# TIDA-01485_Page2.net
KiCad netlist of a schematic drawn in Altium Designer
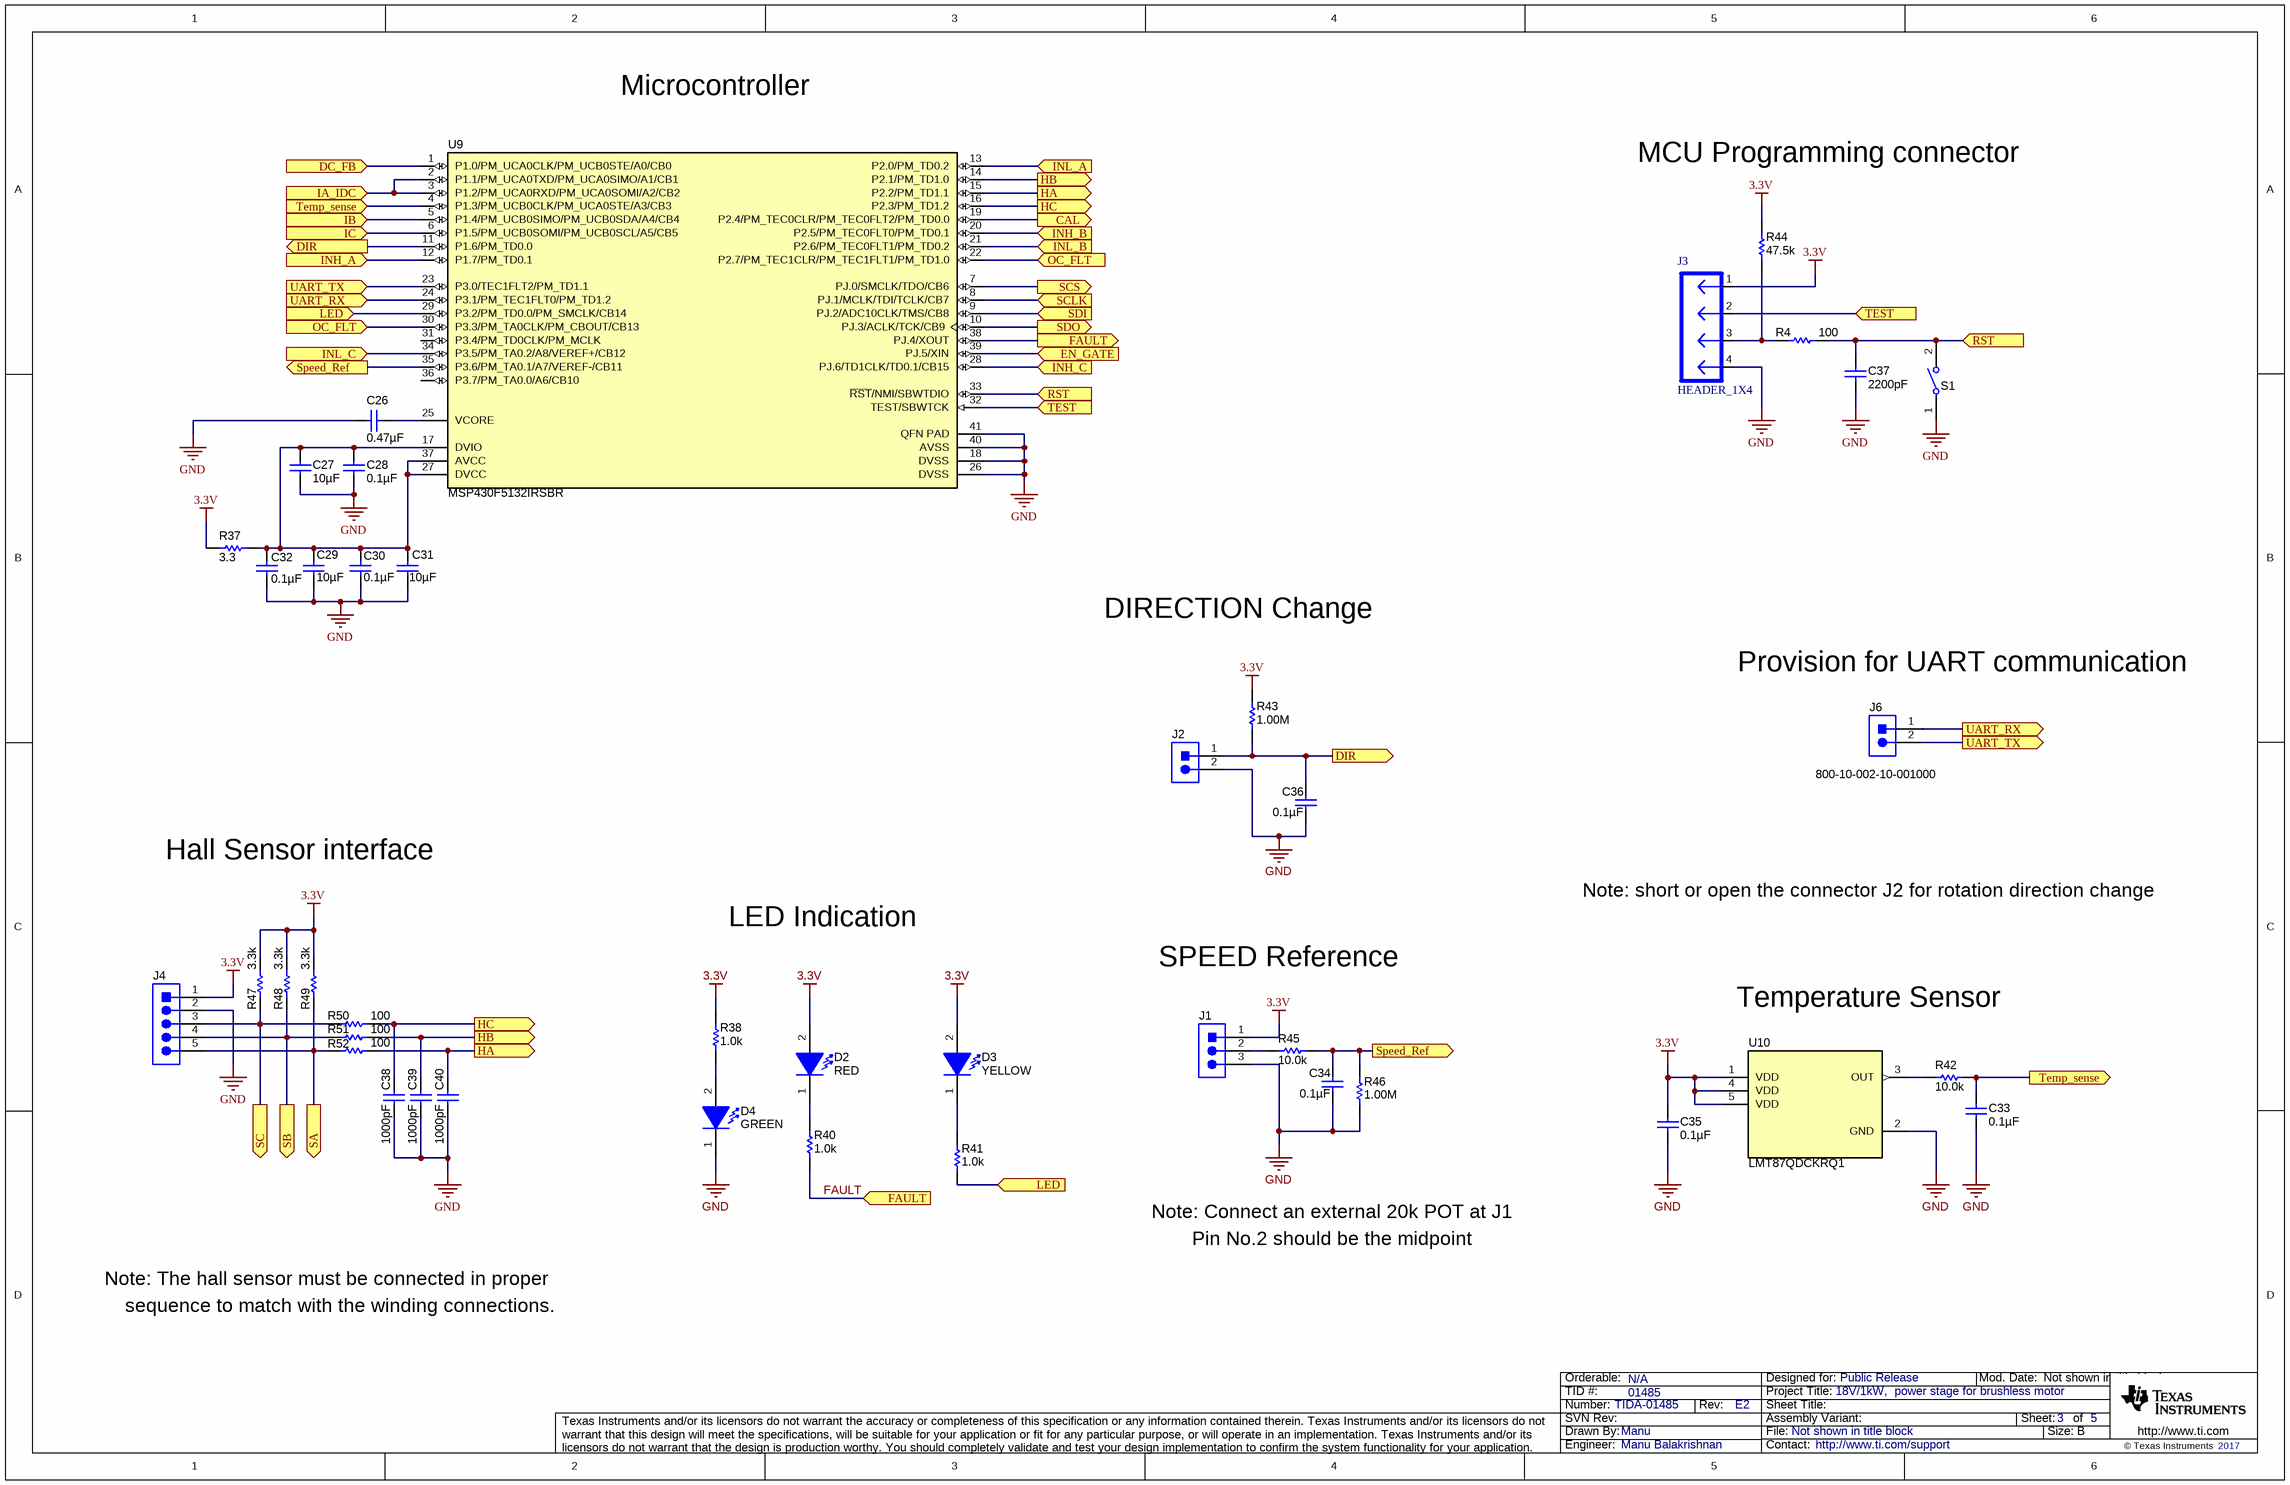
[diagram p0: TIDA-01485_Page2.SchDoc]

(export (version "E")
  (design (tool "Eeschema 10.0.6"))
  (components
    (comp (ref "C26")
      (value "C0805C474K4RACTU")
      (footprint "0805_HV")
      (description "CAP, CERM, 0.47 µF, 16 V, +/- 10%, X7R, 0805")
      (fields
        (field (name "VALUEDISPLAYED") "0.47µF")
        (field (name "MANUFACTURER") "Kemet")
        (field (name "PUBLISHER") "Texas Instruments")
      )
      (libsource (lib "Capacitor_Ceramic") (part "C0805C474K4RACTU"))
    )
    (comp (ref "C27")
      (value "0805YD106MAT2A")
      (footprint "0805_HV")
      (description "CAP, CERM, 10uF, 16V, +/-20%, X5R, 0805")
      (fields
        (field (name "VALUEDISPLAYED") "10µF")
        (field (name "MANUFACTURER") "AVX")
        (field (name "PUBLISHER") "Texas Instruments")
      )
      (libsource (lib "Capacitor_Ceramic") (part "0805YD106MAT2A"))
    )
    (comp (ref "C28")
      (value "0603YC104JAT2A")
      (footprint "0603")
      (description "CAP, CERM, 0.1 µF, 16 V, +/- 5%, X7R, 0603")
      (fields
        (field (name "VALUEDISPLAYED") "0.1µF")
        (field (name "MANUFACTURER") "AVX")
        (field (name "PUBLISHER") "Texas Instruments")
      )
      (libsource (lib "Capacitor_Ceramic") (part "0603YC104JAT2A"))
    )
    (comp (ref "C29")
      (value "0805YD106MAT2A")
      (footprint "0805_HV")
      (description "CAP, CERM, 10uF, 16V, +/-20%, X5R, 0805")
      (fields
        (field (name "VALUEDISPLAYED") "10µF")
        (field (name "MANUFACTURER") "AVX")
        (field (name "PUBLISHER") "Texas Instruments")
      )
      (libsource (lib "Capacitor_Ceramic") (part "0805YD106MAT2A"))
    )
    (comp (ref "C30")
      (value "0603YC104JAT2A")
      (footprint "0603")
      (description "CAP, CERM, 0.1 µF, 16 V, +/- 5%, X7R, 0603")
      (fields
        (field (name "VALUEDISPLAYED") "0.1µF")
        (field (name "MANUFACTURER") "AVX")
        (field (name "PUBLISHER") "Texas Instruments")
      )
      (libsource (lib "Capacitor_Ceramic") (part "0603YC104JAT2A"))
    )
    (comp (ref "C31")
      (value "0805YD106MAT2A")
      (footprint "0805_HV")
      (description "CAP, CERM, 10uF, 16V, +/-20%, X5R, 0805")
      (fields
        (field (name "VALUEDISPLAYED") "10µF")
        (field (name "MANUFACTURER") "AVX")
        (field (name "PUBLISHER") "Texas Instruments")
      )
      (libsource (lib "Capacitor_Ceramic") (part "0805YD106MAT2A"))
    )
    (comp (ref "C32")
      (value "0603YC104JAT2A")
      (footprint "0603")
      (description "CAP, CERM, 0.1 µF, 16 V, +/- 5%, X7R, 0603")
      (fields
        (field (name "VALUEDISPLAYED") "0.1µF")
        (field (name "MANUFACTURER") "AVX")
        (field (name "PUBLISHER") "Texas Instruments")
      )
      (libsource (lib "Capacitor_Ceramic") (part "0603YC104JAT2A"))
    )
    (comp (ref "C33")
      (value "885012105016")
      (footprint "0402")
      (description "CAP, CERM, 0.1 µF, 16 V, +/- 20%, X5R, 0402")
      (fields
        (field (name "VALUEDISPLAYED") "0.1µF")
        (field (name "MANUFACTURER") "Wurth Elektronik")
        (field (name "PUBLISHER") "Texas Instruments")
      )
      (libsource (lib "Capacitor_Ceramic") (part "885012105016"))
    )
    (comp (ref "C34")
      (value "885012105016")
      (footprint "0402")
      (description "CAP, CERM, 0.1 µF, 16 V, +/- 20%, X5R, 0402")
      (fields
        (field (name "VALUEDISPLAYED") "0.1µF")
        (field (name "MANUFACTURER") "Wurth Elektronik")
        (field (name "PUBLISHER") "Texas Instruments")
      )
      (libsource (lib "Capacitor_Ceramic") (part "885012105016"))
    )
    (comp (ref "C35")
      (value "885012105016")
      (footprint "0402")
      (description "CAP, CERM, 0.1 µF, 16 V, +/- 20%, X5R, 0402")
      (fields
        (field (name "VALUEDISPLAYED") "0.1µF")
        (field (name "MANUFACTURER") "Wurth Elektronik")
        (field (name "PUBLISHER") "Texas Instruments")
      )
      (libsource (lib "Capacitor_Ceramic") (part "885012105016"))
    )
    (comp (ref "C36")
      (value "885012105016")
      (footprint "0402")
      (description "CAP, CERM, 0.1 µF, 16 V, +/- 20%, X5R, 0402")
      (fields
        (field (name "VALUEDISPLAYED") "0.1µF")
        (field (name "MANUFACTURER") "Wurth Elektronik")
        (field (name "PUBLISHER") "Texas Instruments")
      )
      (libsource (lib "Capacitor_Ceramic") (part "885012105016"))
    )
    (comp (ref "C37")
      (value "GRM155R71H222KA01D")
      (footprint "0402")
      (description "CAP, CERM, 2200 pF, 50 V, +/- 10%, X7R, 0402")
      (fields
        (field (name "VALUEDISPLAYED") "2200pF")
        (field (name "MANUFACTURER") "MuRata")
        (field (name "PUBLISHER") "Texas Instruments")
      )
      (libsource (lib "Capacitor_Ceramic") (part "GRM155R71H222KA01D"))
    )
    (comp (ref "C38")
      (value "885012205061")
      (footprint "0402")
      (description "CAP, CERM, 1000 pF, 50 V, +/- 10%, X7R, 0402")
      (fields
        (field (name "VALUEDISPLAYED") "1000pF")
        (field (name "MANUFACTURER") "Wurth Elektronik")
        (field (name "PUBLISHER") "Texas Instruments")
      )
      (libsource (lib "Capacitor_Ceramic") (part "885012205061"))
    )
    (comp (ref "C39")
      (value "885012205061")
      (footprint "0402")
      (description "CAP, CERM, 1000 pF, 50 V, +/- 10%, X7R, 0402")
      (fields
        (field (name "VALUEDISPLAYED") "1000pF")
        (field (name "MANUFACTURER") "Wurth Elektronik")
        (field (name "PUBLISHER") "Texas Instruments")
      )
      (libsource (lib "Capacitor_Ceramic") (part "885012205061"))
    )
    (comp (ref "C40")
      (value "885012205061")
      (footprint "0402")
      (description "CAP, CERM, 1000 pF, 50 V, +/- 10%, X7R, 0402")
      (fields
        (field (name "VALUEDISPLAYED") "1000pF")
        (field (name "MANUFACTURER") "Wurth Elektronik")
        (field (name "PUBLISHER") "Texas Instruments")
      )
      (libsource (lib "Capacitor_Ceramic") (part "885012205061"))
    )
    (comp (ref "D2")
      (value "RED")
      (footprint "WL-SMCW_GREEN")
      (description "LED RED CLEAR 0603 SMD")
      (fields
        (field (name "MANUFACTURER") "Wurth Elektronics Inc")
        (field (name "PARTNUMBER") "150060RS75000")
        (field (name "PUBLISHER") "Texas Instruments")
      )
      (libsource (lib "LED") (part "150060GS75000"))
    )
    (comp (ref "D3")
      (value "YELLOW")
      (footprint "WL-SMCW_GREEN")
      (description "LED YELLOW CLEAR 0603 SMD")
      (fields
        (field (name "MANUFACTURER") "Wurth Elektronics Inc")
        (field (name "PARTNUMBER") "150060YS75000")
        (field (name "PUBLISHER") "Texas Instruments")
      )
      (libsource (lib "LED") (part "150060GS75000"))
    )
    (comp (ref "D4")
      (value "GREEN")
      (footprint "WL-SMCW_GREEN")
      (description "LED, Green, SMD")
      (fields
        (field (name "MANUFACTURER") "Wurth Elektronics Inc")
        (field (name "PARTNUMBER") "150060GS75000")
        (field (name "PUBLISHER") "Texas Instruments")
      )
      (libsource (lib "LED") (part "150060GS75000"))
    )
    (comp (ref "J1")
      (value "800-10-003-10-001000")
      (footprint "Mill-Max_800-10-003-10-001000")
      (description "Header, 100mil, 3x1, TH")
      (fields
        (field (name "MANUFACTURER") "Mill-Max")
        (field (name "SYMBOLCREATOR") "a0799628")
        (field (name "PUBLISHER") "Texas Instruments")
      )
      (libsource (lib "Connectors") (part "800-10-003-10-001000"))
    )
    (comp (ref "J2")
      (value "800-10-002-10-001000")
      (footprint "Mill-Max_800-10-002-10-001000")
      (description "Header, 100mil, 2x1, TH")
      (fields
        (field (name "MANUFACTURER") "Mill-Max")
        (field (name "SYMBOLCREATOR") "a0412235")
        (field (name "PUBLISHER") "Texas Instruments")
      )
      (libsource (lib "TIDA-00472") (part "800-10-002-10-001000"))
    )
    (comp (ref "J3")
      (value "HEADER_1X4")
      (footprint "Mill-Max_800-10-004-10-001000")
      (description "Header, Male 4-pin, 100mil spacing,")
      (fields (field (name "MANUFACTURER") "Sullins") (field (name "PARTNUMBER") "PEC04SAAN"))
      (libsource (lib "PADSlegacy_Hardware") (part "HEADER_1X4"))
    )
    (comp (ref "J4")
      (value "800-10-005-10-001000")
      (footprint "Mill-Max_800-10-005-10-001000")
      (description "Header, 100mil, 5x1, TH")
      (fields
        (field (name "MANUFACTURER") "Mill-Max")
        (field (name "SYMBOLCREATOR") "a0412235")
        (field (name "PUBLISHER") "Texas Instruments")
      )
      (libsource (lib "Connectors_Mill_Max") (part "800-10-005-10-001000"))
    )
    (comp (ref "J6")
      (value "800-10-002-10-001000")
      (footprint "Mill-Max_800-10-002-10-001000")
      (description "Header, 100mil, 2x1, TH")
      (fields
        (field (name "MANUFACTURER") "Mill-Max")
        (field (name "SYMBOLCREATOR") "a0412235")
        (field (name "PUBLISHER") "Texas Instruments")
      )
      (libsource (lib "TIDA-00472") (part "800-10-002-10-001000"))
    )
    (comp (ref "R4")
      (value "ERJ-2RKF1000X")
      (footprint "0402")
      (description "RES, 100, 1%, 0.1 W, 0402")
      (fields
        (field (name "VALUEDISPLAYED") "100")
        (field (name "MANUFACTURER") "Panasonic")
        (field (name "PUBLISHER") "Texas Instruments")
      )
      (libsource (lib "Resistor_0402") (part "ERJ-2RKF1000X"))
    )
    (comp (ref "R37")
      (value "CRCW06033R30JNEA")
      (footprint "0603")
      (description "RES, 3.3, 5%, 0.1 W, 0603")
      (fields
        (field (name "VALUEDISPLAYED") "3.3")
        (field (name "MANUFACTURER") "Vishay-Dale")
        (field (name "PUBLISHER") "Texas Instruments")
      )
      (libsource (lib "Resistor_0603") (part "CRCW06033R30JNEA"))
    )
    (comp (ref "R38")
      (value "CRCW06031K00JNEA")
      (footprint "0603")
      (description "RES, 1.0 k, 5%, 0.1 W, 0603")
      (fields
        (field (name "VALUEDISPLAYED") "1.0k")
        (field (name "MANUFACTURER") "Vishay-Dale")
        (field (name "PUBLISHER") "Texas Instruments")
      )
      (libsource (lib "Resistor_0603") (part "CRCW06031K00JNEA"))
    )
    (comp (ref "R40")
      (value "CRCW06031K00JNEA")
      (footprint "0603")
      (description "RES, 1.0 k, 5%, 0.1 W, 0603")
      (fields
        (field (name "VALUEDISPLAYED") "1.0k")
        (field (name "MANUFACTURER") "Vishay-Dale")
        (field (name "PUBLISHER") "Texas Instruments")
      )
      (libsource (lib "Resistor_0603") (part "CRCW06031K00JNEA"))
    )
    (comp (ref "R41")
      (value "CRCW06031K00JNEA")
      (footprint "0603")
      (description "RES, 1.0 k, 5%, 0.1 W, 0603")
      (fields
        (field (name "VALUEDISPLAYED") "1.0k")
        (field (name "MANUFACTURER") "Vishay-Dale")
        (field (name "PUBLISHER") "Texas Instruments")
      )
      (libsource (lib "Resistor_0603") (part "CRCW06031K00JNEA"))
    )
    (comp (ref "R42")
      (value "CRCW040210K0FKED")
      (footprint "0402")
      (description "RES, 10.0 k, 1%, 0.063 W, 0402")
      (fields
        (field (name "VALUEDISPLAYED") "10.0k")
        (field (name "MANUFACTURER") "Vishay-Dale")
        (field (name "PUBLISHER") "Texas Instruments")
      )
      (libsource (lib "Resistor_0402") (part "CRCW040210K0FKED"))
    )
    (comp (ref "R43")
      (value "ERJ-2RKF1004X")
      (footprint "0402")
      (description "RES, 1.00 M, 1%, 0.1 W, 0402")
      (fields
        (field (name "VALUEDISPLAYED") "1.00M")
        (field (name "MANUFACTURER") "Panasonic")
        (field (name "PUBLISHER") "Texas Instruments")
      )
      (libsource (lib "Resistor_0402") (part "ERJ-2RKF1004X"))
    )
    (comp (ref "R44")
      (value "CRCW040247K5FKED")
      (footprint "0402")
      (description "RES, 47.5 k, 1%, 0.063 W, 0402")
      (fields
        (field (name "MANUFACTURER") "Vishay-Dale")
        (field (name "VALUEDISPLAYED") "47.5k")
        (field (name "PUBLISHER") "Texas Instruments")
      )
      (libsource (lib "Resistor_0402") (part "CRCW040247K5FKED"))
    )
    (comp (ref "R45")
      (value "CRCW040210K0FKED")
      (footprint "0402")
      (description "RES, 10.0 k, 1%, 0.063 W, 0402")
      (fields
        (field (name "VALUEDISPLAYED") "10.0k")
        (field (name "MANUFACTURER") "Vishay-Dale")
        (field (name "PUBLISHER") "Texas Instruments")
      )
      (libsource (lib "Resistor_0402") (part "CRCW040210K0FKED"))
    )
    (comp (ref "R46")
      (value "ERJ-2RKF1004X")
      (footprint "0402")
      (description "RES, 1.00 M, 1%, 0.1 W, 0402")
      (fields
        (field (name "VALUEDISPLAYED") "1.00M")
        (field (name "MANUFACTURER") "Panasonic")
        (field (name "PUBLISHER") "Texas Instruments")
      )
      (libsource (lib "Resistor_0402") (part "ERJ-2RKF1004X"))
    )
    (comp (ref "R47")
      (value "CRCW04023K30JNED")
      (footprint "0402")
      (description "RES, 3.3 k, 5%, 0.063 W, 0402")
      (fields
        (field (name "VALUEDISPLAYED") "3.3k")
        (field (name "MANUFACTURER") "Vishay-Dale")
        (field (name "PUBLISHER") "Texas Instruments")
      )
      (libsource (lib "Resistor_0402") (part "CRCW04023K30JNED"))
    )
    (comp (ref "R48")
      (value "CRCW04023K30JNED")
      (footprint "0402")
      (description "RES, 3.3 k, 5%, 0.063 W, 0402")
      (fields
        (field (name "VALUEDISPLAYED") "3.3k")
        (field (name "MANUFACTURER") "Vishay-Dale")
        (field (name "PUBLISHER") "Texas Instruments")
      )
      (libsource (lib "Resistor_0402") (part "CRCW04023K30JNED"))
    )
    (comp (ref "R49")
      (value "CRCW04023K30JNED")
      (footprint "0402")
      (description "RES, 3.3 k, 5%, 0.063 W, 0402")
      (fields
        (field (name "VALUEDISPLAYED") "3.3k")
        (field (name "MANUFACTURER") "Vishay-Dale")
        (field (name "PUBLISHER") "Texas Instruments")
      )
      (libsource (lib "Resistor_0402") (part "CRCW04023K30JNED"))
    )
    (comp (ref "R50")
      (value "ERJ-2RKF1000X")
      (footprint "0402")
      (description "RES, 100, 1%, 0.1 W, 0402")
      (fields
        (field (name "VALUEDISPLAYED") "100")
        (field (name "MANUFACTURER") "Panasonic")
        (field (name "PUBLISHER") "Texas Instruments")
      )
      (libsource (lib "Resistor_0402") (part "ERJ-2RKF1000X"))
    )
    (comp (ref "R51")
      (value "ERJ-2RKF1000X")
      (footprint "0402")
      (description "RES, 100, 1%, 0.1 W, 0402")
      (fields
        (field (name "VALUEDISPLAYED") "100")
        (field (name "MANUFACTURER") "Panasonic")
        (field (name "PUBLISHER") "Texas Instruments")
      )
      (libsource (lib "Resistor_0402") (part "ERJ-2RKF1000X"))
    )
    (comp (ref "R52")
      (value "ERJ-2RKF1000X")
      (footprint "0402")
      (description "RES, 100, 1%, 0.1 W, 0402")
      (fields
        (field (name "VALUEDISPLAYED") "100")
        (field (name "MANUFACTURER") "Panasonic")
        (field (name "PUBLISHER") "Texas Instruments")
      )
      (libsource (lib "Resistor_0402") (part "ERJ-2RKF1000X"))
    )
    (comp (ref "S1")
      (value "434121025816")
      (footprint "SW_434121025816")
      (description "Switch, Tactile, SPST, 12 V, SMD")
      (fields
        (field (name "MANUFACTURER") "Wurth Elektronik")
        (field (name "SYMBOLCREATOR") "a0799628")
        (field (name "PUBLISHER") "Texas Instruments")
      )
      (libsource (lib "Switches") (part "434121025816"))
    )
    (comp (ref "U9")
      (value "MSP430F5132IRSBR")
      (footprint "RSB0040B")
      (fields
        (field (name "ALTERNATE PARTNUMBER") "Equivalent")
        (field (name "MANUFACTURER") "Texas Instruments")
      )
      (libsource (lib "TI MCU MSP430") (part "MSP430F5132IRSBR"))
    )
    (comp (ref "U10")
      (value "LMT87QDCKRQ1")
      (footprint "DCK0005A_N")
      (description "SC70 Analog Temperature Sensor with Class-AB Output, DCK0005A")
      (fields
        (field (name "ALTERNATE PARTNUMBER") "LMT87QDCKTQ1")
        (field (name "MANUFACTURER") "Texas Instruments")
        (field (name "SYMBOLCREATOR") "a0411947")
        (field (name "PUBLISHER") "Texas Instruments")
      )
      (libsource (lib "TI_Pre_Release") (part "LMT87QDCKRQ1"))
    )
  )
  (nets
    (net (code "1") (name "/CAL") (class "Default")
      (node (ref "U9") (pin "19") (pinfunction "P2.4/PM_TEC0CLR/PM_TEC0FLT2/PM_TD0.0_19") (pintype "bidirectional"))
    )
    (net (code "2") (name "/DC_FB") (class "Default")
      (node (ref "U9") (pin "1") (pinfunction "P1.0/PM_UCA0CLK/PM_UCB0STE/A0/CB0_1") (pintype "bidirectional"))
    )
    (net (code "3") (name "/DIR") (class "Default")
      (node (ref "C36") (pin "1") (pinfunction "1_1") (pintype "passive"))
      (node (ref "J2") (pin "1") (pinfunction "1_1") (pintype "passive"))
      (node (ref "R43") (pin "2") (pinfunction "2_2") (pintype "passive"))
      (node (ref "U9") (pin "11") (pinfunction "P1.6/PM_TD0.0_11") (pintype "bidirectional"))
    )
    (net (code "4") (name "/EN_GATE") (class "Default")
      (node (ref "U9") (pin "39") (pinfunction "PJ.5/XIN_39") (pintype "bidirectional"))
    )
    (net (code "5") (name "/FAULT") (class "Default")
      (node (ref "R40") (pin "1") (pinfunction "1_1") (pintype "passive"))
      (node (ref "U9") (pin "38") (pinfunction "PJ.4/XOUT_38") (pintype "bidirectional"))
    )
    (net (code "6") (name "/HA") (class "Default")
      (node (ref "C40") (pin "1") (pinfunction "1_1") (pintype "passive"))
      (node (ref "R52") (pin "1") (pinfunction "1_1") (pintype "passive"))
      (node (ref "U9") (pin "15") (pinfunction "P2.2/PM_TD1.1_15") (pintype "bidirectional"))
    )
    (net (code "7") (name "/HB") (class "Default")
      (node (ref "C39") (pin "1") (pinfunction "1_1") (pintype "passive"))
      (node (ref "R51") (pin "1") (pinfunction "1_1") (pintype "passive"))
      (node (ref "U9") (pin "14") (pinfunction "P2.1/PM_TD1.0_14") (pintype "bidirectional"))
    )
    (net (code "8") (name "/HC") (class "Default")
      (node (ref "C38") (pin "1") (pinfunction "1_1") (pintype "passive"))
      (node (ref "R50") (pin "1") (pinfunction "1_1") (pintype "passive"))
      (node (ref "U9") (pin "16") (pinfunction "P2.3/PM_TD1.2_16") (pintype "bidirectional"))
    )
    (net (code "9") (name "/IA_IDC") (class "Default")
      (node (ref "U9") (pin "2") (pinfunction "P1.1/PM_UCA0TXD/PM_UCA0SIMO/A1/CB1_2") (pintype "bidirectional"))
      (node (ref "U9") (pin "3") (pinfunction "P1.2/PM_UCA0RXD/PM_UCA0SOMI/A2/CB2_3") (pintype "bidirectional"))
    )
    (net (code "10") (name "/IB") (class "Default")
      (node (ref "U9") (pin "5") (pinfunction "P1.4/PM_UCB0SIMO/PM_UCB0SDA/A4/CB4_5") (pintype "bidirectional"))
    )
    (net (code "11") (name "/IC") (class "Default")
      (node (ref "U9") (pin "6") (pinfunction "P1.5/PM_UCB0SOMI/PM_UCB0SCL/A5/CB5_6") (pintype "bidirectional"))
    )
    (net (code "12") (name "/INH_A") (class "Default")
      (node (ref "U9") (pin "12") (pinfunction "P1.7/PM_TD0.1_12") (pintype "bidirectional"))
    )
    (net (code "13") (name "/INH_B") (class "Default")
      (node (ref "U9") (pin "20") (pinfunction "P2.5/PM_TEC0FLT0/PM_TD0.1_20") (pintype "bidirectional"))
    )
    (net (code "14") (name "/INH_C") (class "Default")
      (node (ref "U9") (pin "28") (pinfunction "PJ.6/TD1CLK/TD0.1/CB15_28") (pintype "bidirectional"))
    )
    (net (code "15") (name "/INL_A") (class "Default")
      (node (ref "U9") (pin "13") (pinfunction "P2.0/PM_TD0.2_13") (pintype "bidirectional"))
    )
    (net (code "16") (name "/INL_B") (class "Default")
      (node (ref "U9") (pin "21") (pinfunction "P2.6/PM_TEC0FLT1/PM_TD0.2_21") (pintype "bidirectional"))
    )
    (net (code "17") (name "/INL_C") (class "Default")
      (node (ref "U9") (pin "34") (pinfunction "P3.5/PM_TA0.2/A8/VEREF+/CB12_34") (pintype "bidirectional"))
    )
    (net (code "18") (name "/LED") (class "Default")
      (node (ref "R41") (pin "1") (pinfunction "1_1") (pintype "passive"))
      (node (ref "U9") (pin "29") (pinfunction "P3.2/PM_TD0.0/PM_SMCLK/CB14_29") (pintype "bidirectional"))
    )
    (net (code "19") (name "/OC_FLT") (class "Default")
      (node (ref "U9") (pin "22") (pinfunction "P2.7/PM_TEC1CLR/PM_TEC1FLT1/PM_TD1.0_22") (pintype "bidirectional"))
      (node (ref "U9") (pin "30") (pinfunction "P3.3/PM_TA0CLK/PM_CBOUT/CB13_30") (pintype "bidirectional"))
    )
    (net (code "20") (name "/RST") (class "Default")
      (node (ref "C37") (pin "1") (pinfunction "1_1") (pintype "passive"))
      (node (ref "R4") (pin "1") (pinfunction "1_1") (pintype "passive"))
      (node (ref "S1") (pin "2") (pinfunction "2_2") (pintype "passive"))
      (node (ref "U9") (pin "33") (pinfunction "~{RST}/NMI/SBWTDIO_33") (pintype "bidirectional"))
    )
    (net (code "21") (name "/SA") (class "Default")
      (node (ref "J4") (pin "5") (pinfunction "5_5") (pintype "passive"))
      (node (ref "R49") (pin "1") (pinfunction "1_1") (pintype "passive"))
      (node (ref "R52") (pin "2") (pinfunction "2_2") (pintype "passive"))
    )
    (net (code "22") (name "/SB") (class "Default")
      (node (ref "J4") (pin "4") (pinfunction "4_4") (pintype "passive"))
      (node (ref "R48") (pin "1") (pinfunction "1_1") (pintype "passive"))
      (node (ref "R51") (pin "2") (pinfunction "2_2") (pintype "passive"))
    )
    (net (code "23") (name "/SC") (class "Default")
      (node (ref "J4") (pin "3") (pinfunction "3_3") (pintype "passive"))
      (node (ref "R47") (pin "1") (pinfunction "1_1") (pintype "passive"))
      (node (ref "R50") (pin "2") (pinfunction "2_2") (pintype "passive"))
    )
    (net (code "24") (name "/SCLK") (class "Default")
      (node (ref "U9") (pin "8") (pinfunction "PJ.1/MCLK/TDI/TCLK/CB7_8") (pintype "bidirectional"))
    )
    (net (code "25") (name "/SCS") (class "Default")
      (node (ref "U9") (pin "7") (pinfunction "PJ.0/SMCLK/TDO/CB6_7") (pintype "bidirectional"))
    )
    (net (code "26") (name "/SDI") (class "Default")
      (node (ref "U9") (pin "9") (pinfunction "PJ.2/ADC10CLK/TMS/CB8_9") (pintype "bidirectional"))
    )
    (net (code "27") (name "/SDO") (class "Default")
      (node (ref "U9") (pin "10") (pinfunction "PJ.3/ACLK/TCK/CB9_10") (pintype "bidirectional"))
    )
    (net (code "28") (name "/Speed_Ref") (class "Default")
      (node (ref "C34") (pin "1") (pinfunction "1_1") (pintype "passive"))
      (node (ref "R45") (pin "1") (pinfunction "1_1") (pintype "passive"))
      (node (ref "R46") (pin "2") (pinfunction "2_2") (pintype "passive"))
      (node (ref "U9") (pin "35") (pinfunction "P3.6/PM_TA0.1/A7/VEREF-/CB11_35") (pintype "bidirectional"))
    )
    (net (code "29") (name "/TEST") (class "Default")
      (node (ref "J3") (pin "2") (pintype "passive"))
      (node (ref "U9") (pin "32") (pinfunction "TEST/SBWTCK_32") (pintype "input"))
    )
    (net (code "30") (name "/Temp_sense") (class "Default")
      (node (ref "C33") (pin "1") (pinfunction "1_1") (pintype "passive"))
      (node (ref "R42") (pin "1") (pinfunction "1_1") (pintype "passive"))
      (node (ref "U9") (pin "4") (pinfunction "P1.3/PM_UCB0CLK/PM_UCA0STE/A3/CB3_4") (pintype "bidirectional"))
    )
    (net (code "31") (name "/UART_RX") (class "Default")
      (node (ref "J6") (pin "1") (pinfunction "1_1") (pintype "passive"))
      (node (ref "U9") (pin "24") (pinfunction "P3.1/PM_TEC1FLT0/PM_TD1.2_24") (pintype "bidirectional"))
    )
    (net (code "32") (name "/UART_TX") (class "Default")
      (node (ref "J6") (pin "2") (pinfunction "2_2") (pintype "passive"))
      (node (ref "U9") (pin "23") (pinfunction "P3.0/TEC1FLT2/PM_TD1.1_23") (pintype "bidirectional"))
    )
    (net (code "33") (name "3.3V") (class "Default")
      (node (ref "C35") (pin "1") (pinfunction "1_1") (pintype "passive"))
      (node (ref "D2") (pin "2") (pinfunction "A_2") (pintype "passive"))
      (node (ref "D3") (pin "2") (pinfunction "A_2") (pintype "passive"))
      (node (ref "J1") (pin "1") (pinfunction "1_1") (pintype "passive"))
      (node (ref "J3") (pin "1") (pintype "passive"))
      (node (ref "J4") (pin "1") (pinfunction "1_1") (pintype "passive"))
      (node (ref "R37") (pin "1") (pinfunction "1_1") (pintype "passive"))
      (node (ref "R38") (pin "2") (pinfunction "2_2") (pintype "passive"))
      (node (ref "R43") (pin "1") (pinfunction "1_1") (pintype "passive"))
      (node (ref "R44") (pin "2") (pinfunction "2_2") (pintype "passive"))
      (node (ref "R47") (pin "2") (pinfunction "2_2") (pintype "passive"))
      (node (ref "R48") (pin "2") (pinfunction "2_2") (pintype "passive"))
      (node (ref "R49") (pin "2") (pinfunction "2_2") (pintype "passive"))
      (node (ref "U10") (pin "1") (pinfunction "VDD_1") (pintype "power_in"))
      (node (ref "U10") (pin "4") (pinfunction "VDD_4") (pintype "power_in"))
      (node (ref "U10") (pin "5") (pinfunction "VDD_5") (pintype "power_in"))
    )
    (net (code "34") (name "GND") (class "Default")
      (node (ref "C26") (pin "2") (pinfunction "2_2") (pintype "passive"))
      (node (ref "C27") (pin "2") (pinfunction "2_2") (pintype "passive"))
      (node (ref "C28") (pin "2") (pinfunction "2_2") (pintype "passive"))
      (node (ref "C29") (pin "2") (pinfunction "2_2") (pintype "passive"))
      (node (ref "C30") (pin "2") (pinfunction "2_2") (pintype "passive"))
      (node (ref "C31") (pin "2") (pinfunction "2_2") (pintype "passive"))
      (node (ref "C32") (pin "2") (pinfunction "2_2") (pintype "passive"))
      (node (ref "C33") (pin "2") (pinfunction "2_2") (pintype "passive"))
      (node (ref "C34") (pin "2") (pinfunction "2_2") (pintype "passive"))
      (node (ref "C35") (pin "2") (pinfunction "2_2") (pintype "passive"))
      (node (ref "C36") (pin "2") (pinfunction "2_2") (pintype "passive"))
      (node (ref "C37") (pin "2") (pinfunction "2_2") (pintype "passive"))
      (node (ref "C38") (pin "2") (pinfunction "2_2") (pintype "passive"))
      (node (ref "C39") (pin "2") (pinfunction "2_2") (pintype "passive"))
      (node (ref "C40") (pin "2") (pinfunction "2_2") (pintype "passive"))
      (node (ref "D4") (pin "1") (pinfunction "K_1") (pintype "passive"))
      (node (ref "J1") (pin "3") (pinfunction "3_3") (pintype "passive"))
      (node (ref "J2") (pin "2") (pinfunction "2_2") (pintype "passive"))
      (node (ref "J3") (pin "4") (pintype "passive"))
      (node (ref "J4") (pin "2") (pinfunction "2_2") (pintype "passive"))
      (node (ref "R46") (pin "1") (pinfunction "1_1") (pintype "passive"))
      (node (ref "S1") (pin "1") (pinfunction "1_1") (pintype "passive"))
      (node (ref "U10") (pin "2") (pinfunction "GND_2") (pintype "power_in"))
      (node (ref "U9") (pin "18") (pinfunction "DVSS_18") (pintype "power_in"))
      (node (ref "U9") (pin "26") (pinfunction "DVSS_26") (pintype "power_in"))
      (node (ref "U9") (pin "40") (pinfunction "AVSS_40") (pintype "power_in"))
      (node (ref "U9") (pin "41") (pinfunction "QFN_PAD_41") (pintype "power_in"))
    )
    (net (code "35") (name "Net-(D2-K)") (class "Default")
      (node (ref "D2") (pin "1") (pinfunction "K_1") (pintype "passive"))
      (node (ref "R40") (pin "2") (pinfunction "2_2") (pintype "passive"))
    )
    (net (code "36") (name "Net-(D3-K)") (class "Default")
      (node (ref "D3") (pin "1") (pinfunction "K_1") (pintype "passive"))
      (node (ref "R41") (pin "2") (pinfunction "2_2") (pintype "passive"))
    )
    (net (code "37") (name "Net-(D4-A)") (class "Default")
      (node (ref "D4") (pin "2") (pinfunction "A_2") (pintype "passive"))
      (node (ref "R38") (pin "1") (pinfunction "1_1") (pintype "passive"))
    )
    (net (code "38") (name "Net-(J1-Pad2)") (class "Default")
      (node (ref "J1") (pin "2") (pinfunction "2_2") (pintype "passive"))
      (node (ref "R45") (pin "2") (pinfunction "2_2") (pintype "passive"))
    )
    (net (code "39") (name "Net-(J3-Pad3)") (class "Default")
      (node (ref "J3") (pin "3") (pintype "passive"))
      (node (ref "R4") (pin "2") (pinfunction "2_2") (pintype "passive"))
      (node (ref "R44") (pin "1") (pinfunction "1_1") (pintype "passive"))
    )
    (net (code "40") (name "Net-(U9-AVCC)") (class "Default")
      (node (ref "C27") (pin "1") (pinfunction "1_1") (pintype "passive"))
      (node (ref "C28") (pin "1") (pinfunction "1_1") (pintype "passive"))
      (node (ref "C29") (pin "1") (pinfunction "1_1") (pintype "passive"))
      (node (ref "C30") (pin "1") (pinfunction "1_1") (pintype "passive"))
      (node (ref "C31") (pin "1") (pinfunction "1_1") (pintype "passive"))
      (node (ref "C32") (pin "1") (pinfunction "1_1") (pintype "passive"))
      (node (ref "R37") (pin "2") (pinfunction "2_2") (pintype "passive"))
      (node (ref "U9") (pin "17") (pinfunction "DVIO_17") (pintype "power_in"))
      (node (ref "U9") (pin "27") (pinfunction "DVCC_27") (pintype "power_in"))
      (node (ref "U9") (pin "37") (pinfunction "AVCC_37") (pintype "power_in"))
    )
    (net (code "41") (name "Net-(U9-VCORE)") (class "Default")
      (node (ref "C26") (pin "1") (pinfunction "1_1") (pintype "passive"))
      (node (ref "U9") (pin "25") (pinfunction "VCORE_25") (pintype "passive"))
    )
    (net (code "42") (name "Net-(U10-OUT)") (class "Default")
      (node (ref "R42") (pin "2") (pinfunction "2_2") (pintype "passive"))
      (node (ref "U10") (pin "3") (pinfunction "OUT_3") (pintype "output"))
    )
    (net (code "43") (name "unconnected-(U9-P3.4{slash}PM_TD0CLK{slash}PM_MCLK-Pad31)") (class "Default")
      (node (ref "U9") (pin "31") (pinfunction "P3.4/PM_TD0CLK/PM_MCLK_31") (pintype "bidirectional"))
    )
    (net (code "44") (name "unconnected-(U9-P3.7{slash}PM_TA0.0{slash}A6{slash}CB10-Pad36)") (class "Default")
      (node (ref "U9") (pin "36") (pinfunction "P3.7/PM_TA0.0/A6/CB10_36") (pintype "bidirectional"))
    )
  )
)
